# lm2941_out5v.net
KiCad netlist of a schematic drawn in EAGLE
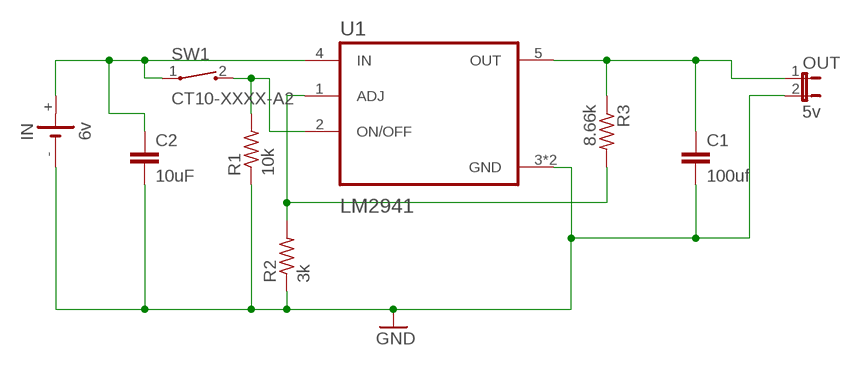
[diagram p0: schematic, sheet 1]

(export (version "E")
  (design (tool "Eeschema 10.0.6"))
  (components
    (comp (ref "C1")
      (value "100uf")
      (footprint "eagle-import:C5B3")
      (libsource (lib "eagle-import") (part "C5/3"))
    )
    (comp (ref "C2")
      (value "10uF")
      (footprint "eagle-import:C5B3")
      (libsource (lib "eagle-import") (part "C5/3"))
    )
    (comp (ref "IN")
      (value "6v")
      (footprint "eagle-import:SL-160AA_PR")
      (libsource (lib "eagle-import") (part "SL-160AA/PR"))
    )
    (comp (ref "OUT")
      (value "5v")
      (footprint "eagle-import:JP1")
      (libsource (lib "eagle-import") (part "JP1E"))
    )
    (comp (ref "R1")
      (value "10k")
      (footprint "eagle-import:0207_10")
      (libsource (lib "eagle-import") (part "R-US_0207/10"))
    )
    (comp (ref "R2")
      (value "3k")
      (footprint "eagle-import:0207_10")
      (libsource (lib "eagle-import") (part "R-US_0207/10"))
    )
    (comp (ref "R3")
      (value "8.66k")
      (footprint "eagle-import:0207_10")
      (libsource (lib "eagle-import") (part "R-US_0207/10"))
    )
    (comp (ref "SW1")
      (value "CT10-XXXX-A2")
      (footprint "eagle-import:CT10-XXXX-A2")
      (libsource (lib "eagle-import") (part "CT10-XXXX-A2"))
    )
    (comp (ref "U1")
      (value "LM2941")
      (footprint "eagle-import:VREG_TPS79625KTTR")
      (fields (field (name "MF") "Texas Instruments") (field (name "MP") "LM2941S"))
      (libsource (lib "eagle-import") (part "LM2941S"))
    )
  )
  (nets
    (net (code "1") (name "GND") (class "Default")
      (node (ref "C1") (pin "2") (pinfunction "2_2") (pintype "passive"))
      (node (ref "C2") (pin "2") (pinfunction "2_2") (pintype "passive"))
      (node (ref "IN") (pin "-") (pinfunction "-_-") (pintype "passive"))
      (node (ref "OUT") (pin "2") (pinfunction "2_2") (pintype "passive"))
      (node (ref "R1") (pin "1") (pinfunction "1_1") (pintype "passive"))
      (node (ref "R2") (pin "1") (pinfunction "1_1") (pintype "passive"))
      (node (ref "U1") (pin "3") (pinfunction "GND_3") (pintype "power_in"))
      (node (ref "U1") (pin "6") (pinfunction "GND_6") (pintype "power_in"))
    )
    (net (code "2") (name "Net-(U1-ADJ)") (class "Default")
      (node (ref "R2") (pin "2") (pinfunction "2_2") (pintype "passive"))
      (node (ref "R3") (pin "2") (pinfunction "2_2") (pintype "passive"))
      (node (ref "U1") (pin "1") (pinfunction "ADJ_1") (pintype "bidirectional"))
    )
    (net (code "3") (name "Net-(U1-IN)") (class "Default")
      (node (ref "C2") (pin "1") (pinfunction "1_1") (pintype "passive"))
      (node (ref "IN") (pin "+") (pinfunction "+_+") (pintype "passive"))
      (node (ref "SW1") (pin "1") (pinfunction "1_1") (pintype "passive"))
      (node (ref "U1") (pin "4") (pinfunction "IN_4") (pintype "input"))
    )
    (net (code "4") (name "Net-(U1-ON{slash}OFF)") (class "Default")
      (node (ref "R1") (pin "2") (pinfunction "2_2") (pintype "passive"))
      (node (ref "SW1") (pin "2") (pinfunction "2_2") (pintype "passive"))
      (node (ref "U1") (pin "2") (pinfunction "ON/OFF_2") (pintype "bidirectional"))
    )
    (net (code "5") (name "Net-(U1-OUT)") (class "Default")
      (node (ref "C1") (pin "1") (pinfunction "1_1") (pintype "passive"))
      (node (ref "OUT") (pin "1") (pinfunction "1_1") (pintype "passive"))
      (node (ref "R3") (pin "1") (pinfunction "1_1") (pintype "passive"))
      (node (ref "U1") (pin "5") (pinfunction "OUT_5") (pintype "output"))
    )
  )
)
